# ESP32C-Mini-MQL-Injection-V2.net
KiCad netlist of a schematic drawn in EAGLE
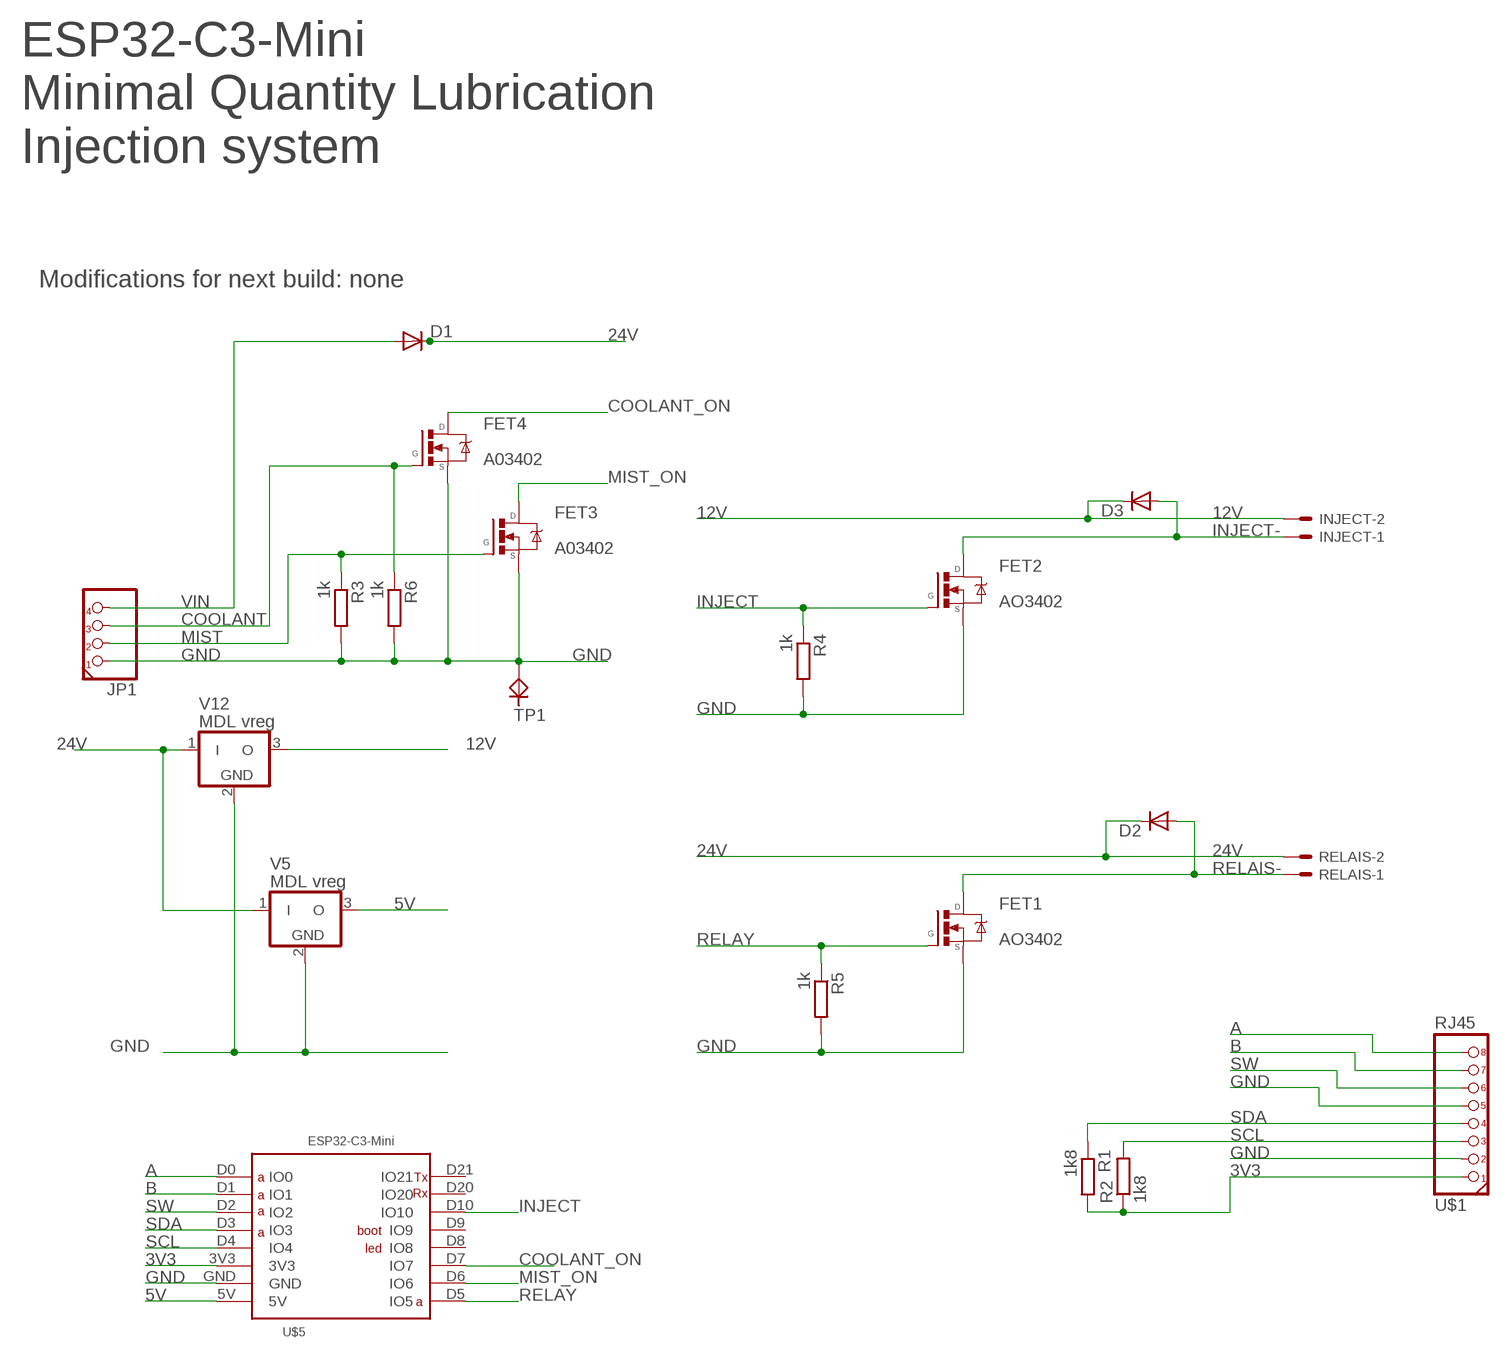
[diagram p0: schematic, sheet 1]

(export (version "E")
  (design (tool "Eeschema 10.0.6"))
  (components
    (comp (ref "D1")
      (value "DIODE-DO214ACI")
      (footprint "eagle-import:DO214ACI")
      (libsource (lib "eagle-import") (part "DIODE-DO214ACI"))
    )
    (comp (ref "D2")
      (value "DIODE-DO214ACI")
      (footprint "eagle-import:DO214ACI")
      (libsource (lib "eagle-import") (part "DIODE-DO214ACI"))
    )
    (comp (ref "D3")
      (value "DIODE-DO214ACI")
      (footprint "eagle-import:DO214ACI")
      (libsource (lib "eagle-import") (part "DIODE-DO214ACI"))
    )
    (comp (ref "FET1")
      (value "AO3402")
      (footprint "eagle-import:SOT23-FET")
      (libsource (lib "eagle-import") (part "NFETHEX-S"))
    )
    (comp (ref "FET2")
      (value "AO3402")
      (footprint "eagle-import:SOT23-FET")
      (libsource (lib "eagle-import") (part "NFETHEX-S"))
    )
    (comp (ref "FET3")
      (value "A03402")
      (footprint "eagle-import:SOT23-FET")
      (libsource (lib "eagle-import") (part "NFETHEX-S"))
    )
    (comp (ref "FET4")
      (value "A03402")
      (footprint "eagle-import:SOT23-FET")
      (libsource (lib "eagle-import") (part "NFETHEX-S"))
    )
    (comp (ref "INJECT")
      (value "JST-XH-02-PIN-L")
      (footprint "eagle-import:JST-XH-02-L")
      (libsource (lib "eagle-import") (part "JST-XH-02-PIN-L"))
    )
    (comp (ref "JP1")
      (value "PINHD-1X4PH254")
      (footprint "eagle-import:1X04_PH254")
      (libsource (lib "eagle-import") (part "PINHD-1X4PH254"))
    )
    (comp (ref "R1")
      (value "1k8")
      (footprint "eagle-import:R0805")
      (libsource (lib "eagle-import") (part "R-EU_R0805"))
    )
    (comp (ref "R2")
      (value "1k8")
      (footprint "eagle-import:R0805")
      (libsource (lib "eagle-import") (part "R-EU_R0805"))
    )
    (comp (ref "R3")
      (value "1k")
      (footprint "eagle-import:R0805")
      (libsource (lib "eagle-import") (part "R-EU_R0805"))
    )
    (comp (ref "R4")
      (value "1k")
      (footprint "eagle-import:R0805")
      (libsource (lib "eagle-import") (part "R-EU_R0805"))
    )
    (comp (ref "R5")
      (value "1k")
      (footprint "eagle-import:R0805")
      (libsource (lib "eagle-import") (part "R-EU_R0805"))
    )
    (comp (ref "R6")
      (value "1k")
      (footprint "eagle-import:R0805")
      (libsource (lib "eagle-import") (part "R-EU_R0805"))
    )
    (comp (ref "RELAIS")
      (value "JST-XH-02-PIN-L")
      (footprint "eagle-import:JST-XH-02-L")
      (libsource (lib "eagle-import") (part "JST-XH-02-PIN-L"))
    )
    (comp (ref "TP1")
      (value "TESTPIN-TP10")
      (footprint "eagle-import:TP10")
      (libsource (lib "eagle-import") (part "TESTPIN-TP10"))
    )
    (comp (ref "U$1")
      (value "RJ45")
      (footprint "eagle-import:RJ45")
      (libsource (lib "eagle-import") (part "RJ45"))
    )
    (comp (ref "U$5")
      (value "ESP32C3MINIL")
      (footprint "eagle-import:ESP32-C3-MINI")
      (libsource (lib "eagle-import") (part "ESP32C3MINIL"))
    )
    (comp (ref "V5")
      (value "MDL vreg")
      (footprint "eagle-import:MDLSTEPDOWNV02")
      (libsource (lib "eagle-import") (part "VREGMDLSTDWNV"))
    )
    (comp (ref "V12")
      (value "MDL vreg")
      (footprint "eagle-import:MDLSTEPDOWNV02")
      (libsource (lib "eagle-import") (part "VREGMDLSTDWNV"))
    )
  )
  (nets
    (net (code "1") (name "/3V3") (class "Default")
      (node (ref "R1") (pin "2") (pinfunction "2_2") (pintype "passive"))
      (node (ref "R2") (pin "1") (pinfunction "1_1") (pintype "passive"))
      (node (ref "U$1") (pin "P$1") (pinfunction "1_P$1") (pintype "passive"))
      (node (ref "U$5") (pin "3V3") (pinfunction "3V3_3V3") (pintype "bidirectional"))
    )
    (net (code "2") (name "/5V") (class "Default")
      (node (ref "U$5") (pin "5V") (pinfunction "5V_5V") (pintype "bidirectional"))
      (node (ref "V5") (pin "3") (pinfunction "O_3") (pintype "passive"))
    )
    (net (code "3") (name "/12V") (class "Default")
      (node (ref "D3") (pin "C") (pinfunction "C_C") (pintype "passive"))
      (node (ref "INJECT") (pin "2") (pinfunction "S_2") (pintype "passive"))
      (node (ref "V12") (pin "3") (pinfunction "O_3") (pintype "passive"))
    )
    (net (code "4") (name "/24V") (class "Default")
      (node (ref "D1") (pin "C") (pinfunction "C_C") (pintype "passive"))
      (node (ref "D2") (pin "C") (pinfunction "C_C") (pintype "passive"))
      (node (ref "RELAIS") (pin "2") (pinfunction "S_2") (pintype "passive"))
      (node (ref "V12") (pin "1") (pinfunction "I_1") (pintype "input"))
      (node (ref "V5") (pin "1") (pinfunction "I_1") (pintype "input"))
    )
    (net (code "5") (name "/A") (class "Default")
      (node (ref "U$1") (pin "P$8") (pinfunction "8_P$8") (pintype "passive"))
      (node (ref "U$5") (pin "D0") (pinfunction "IO0_D0") (pintype "bidirectional"))
    )
    (net (code "6") (name "/B") (class "Default")
      (node (ref "U$1") (pin "P$7") (pinfunction "7_P$7") (pintype "passive"))
      (node (ref "U$5") (pin "D1") (pinfunction "IO1_D1") (pintype "bidirectional"))
    )
    (net (code "7") (name "/COOLANT") (class "Default")
      (node (ref "FET4") (pin "G") (pinfunction "G_G") (pintype "passive"))
      (node (ref "JP1") (pin "3") (pinfunction "3_3") (pintype "passive"))
      (node (ref "R6") (pin "1") (pinfunction "1_1") (pintype "passive"))
    )
    (net (code "8") (name "/COOLANT_ON") (class "Default")
      (node (ref "FET4") (pin "D") (pinfunction "D_D") (pintype "passive"))
      (node (ref "U$5") (pin "D7") (pinfunction "IO7_D7") (pintype "bidirectional"))
    )
    (net (code "9") (name "/GND") (class "Default")
      (node (ref "FET1") (pin "S") (pinfunction "S_S") (pintype "passive"))
      (node (ref "FET2") (pin "S") (pinfunction "S_S") (pintype "passive"))
      (node (ref "FET3") (pin "S") (pinfunction "S_S") (pintype "passive"))
      (node (ref "FET4") (pin "S") (pinfunction "S_S") (pintype "passive"))
      (node (ref "JP1") (pin "1") (pinfunction "1_1") (pintype "passive"))
      (node (ref "R3") (pin "2") (pinfunction "2_2") (pintype "passive"))
      (node (ref "R4") (pin "2") (pinfunction "2_2") (pintype "passive"))
      (node (ref "R5") (pin "2") (pinfunction "2_2") (pintype "passive"))
      (node (ref "R6") (pin "2") (pinfunction "2_2") (pintype "passive"))
      (node (ref "TP1") (pin "TP") (pinfunction "P$1_TP") (pintype "passive"))
      (node (ref "U$1") (pin "P$2") (pinfunction "2_P$2") (pintype "passive"))
      (node (ref "U$1") (pin "P$5") (pinfunction "5_P$5") (pintype "passive"))
      (node (ref "U$5") (pin "GND") (pinfunction "GND_GND") (pintype "bidirectional"))
      (node (ref "V12") (pin "2") (pinfunction "GND_2") (pintype "passive"))
      (node (ref "V5") (pin "2") (pinfunction "GND_2") (pintype "passive"))
    )
    (net (code "10") (name "/INJECT") (class "Default")
      (node (ref "FET2") (pin "G") (pinfunction "G_G") (pintype "passive"))
      (node (ref "R4") (pin "1") (pinfunction "1_1") (pintype "passive"))
      (node (ref "U$5") (pin "D10") (pinfunction "IO10_D10") (pintype "bidirectional"))
    )
    (net (code "11") (name "/INJECT-") (class "Default")
      (node (ref "D3") (pin "A") (pinfunction "A_A") (pintype "passive"))
      (node (ref "FET2") (pin "D") (pinfunction "D_D") (pintype "passive"))
      (node (ref "INJECT") (pin "1") (pinfunction "S_1") (pintype "passive"))
    )
    (net (code "12") (name "/MIST") (class "Default")
      (node (ref "FET3") (pin "G") (pinfunction "G_G") (pintype "passive"))
      (node (ref "JP1") (pin "2") (pinfunction "2_2") (pintype "passive"))
      (node (ref "R3") (pin "1") (pinfunction "1_1") (pintype "passive"))
    )
    (net (code "13") (name "/MIST_ON") (class "Default")
      (node (ref "FET3") (pin "D") (pinfunction "D_D") (pintype "passive"))
      (node (ref "U$5") (pin "D6") (pinfunction "IO6_D6") (pintype "bidirectional"))
    )
    (net (code "14") (name "/RELAIS-") (class "Default")
      (node (ref "D2") (pin "A") (pinfunction "A_A") (pintype "passive"))
      (node (ref "FET1") (pin "D") (pinfunction "D_D") (pintype "passive"))
      (node (ref "RELAIS") (pin "1") (pinfunction "S_1") (pintype "passive"))
    )
    (net (code "15") (name "/RELAY") (class "Default")
      (node (ref "FET1") (pin "G") (pinfunction "G_G") (pintype "passive"))
      (node (ref "R5") (pin "1") (pinfunction "1_1") (pintype "passive"))
      (node (ref "U$5") (pin "D5") (pinfunction "IO5_D5") (pintype "bidirectional"))
    )
    (net (code "16") (name "/SCL") (class "Default")
      (node (ref "R2") (pin "2") (pinfunction "2_2") (pintype "passive"))
      (node (ref "U$1") (pin "P$3") (pinfunction "3_P$3") (pintype "passive"))
      (node (ref "U$5") (pin "D4") (pinfunction "IO4_D4") (pintype "bidirectional"))
    )
    (net (code "17") (name "/SDA") (class "Default")
      (node (ref "R1") (pin "1") (pinfunction "1_1") (pintype "passive"))
      (node (ref "U$1") (pin "P$4") (pinfunction "4_P$4") (pintype "passive"))
      (node (ref "U$5") (pin "D3") (pinfunction "IO3_D3") (pintype "bidirectional"))
    )
    (net (code "18") (name "/SW") (class "Default")
      (node (ref "U$1") (pin "P$6") (pinfunction "6_P$6") (pintype "passive"))
      (node (ref "U$5") (pin "D2") (pinfunction "IO2_D2") (pintype "bidirectional"))
    )
    (net (code "19") (name "/VIN") (class "Default")
      (node (ref "D1") (pin "A") (pinfunction "A_A") (pintype "passive"))
      (node (ref "JP1") (pin "4") (pinfunction "4_4") (pintype "passive"))
    )
    (net (code "20") (name "unconnected-(U$5-IO8-PadD8)") (class "Default")
      (node (ref "U$5") (pin "D8") (pinfunction "IO8_D8") (pintype "bidirectional"))
    )
    (net (code "21") (name "unconnected-(U$5-IO9-PadD9)") (class "Default")
      (node (ref "U$5") (pin "D9") (pinfunction "IO9_D9") (pintype "bidirectional"))
    )
    (net (code "22") (name "unconnected-(U$5-IO20-PadD20)") (class "Default")
      (node (ref "U$5") (pin "D20") (pinfunction "IO20_D20") (pintype "bidirectional"))
    )
    (net (code "23") (name "unconnected-(U$5-IO21-PadD21)") (class "Default")
      (node (ref "U$5") (pin "D21") (pinfunction "IO21_D21") (pintype "bidirectional"))
    )
  )
)
